# Sheet_2_2022-11-04.net
KiCad netlist of a schematic drawn in Altium Designer
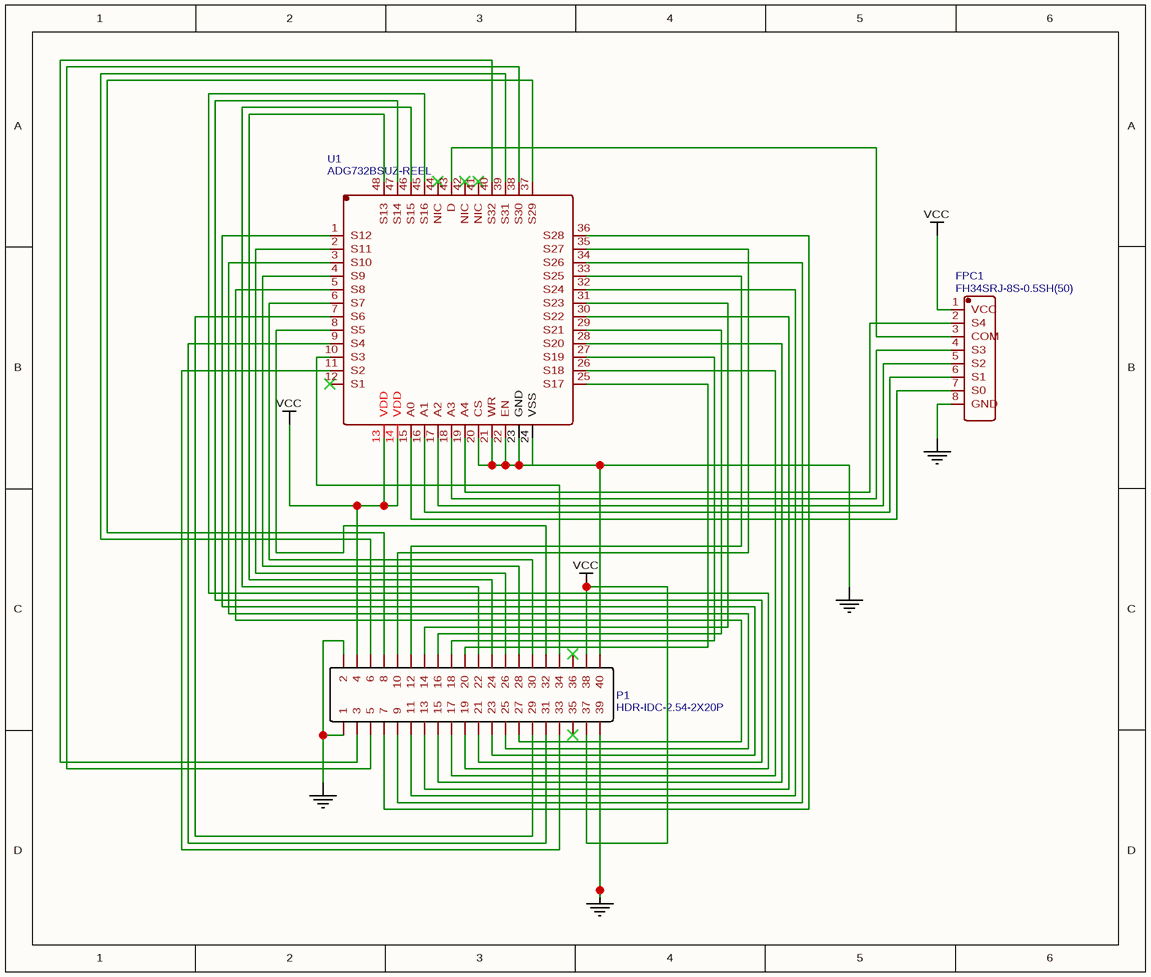
[diagram p0: Sheet_2_2022-11-04.schdoc]

(export (version "E")
  (design (tool "Eeschema 10.0.6"))
  (components
    (comp (ref "FPC1")
      (value "FH34SRJ-8S-0.5SH(50)")
      (fields (field (name "BOM_SUPPLIER PART") "C88372") (field (name "CONTRIBUTOR") "LCSC"))
      (libsource (lib "altium-import") (part "root_0_FH34SRJ-8S-0.5SH(50)_"))
    )
    (comp (ref "P1")
      (value "HDR-IDC-2.54-2X20P")
      (fields
        (field (name "BOM_MANUFACTURER PART") "IDC Box 2X20 2.54MM")
        (field (name "BOM_SUPPLIER PART") "C9138")
      )
      (libsource (lib "altium-import") (part "root_1_HDR-IDC-2.54-2X20P_"))
    )
    (comp (ref "U1")
      (value "ADG732BSUZ-REEL")
      (fields (field (name "BOM_SUPPLIER PART") "C114845") (field (name "CONTRIBUTOR") "LCSC"))
      (libsource (lib "altium-import") (part "root_0_ADG732BSUZ-REEL_"))
    )
  )
  (nets
    (net (code "1") (name "GND") (class "Default")
      (node (ref "FPC1") (pin "8") (pinfunction "GND_8") (pintype "passive"))
      (node (ref "P1") (pin "1") (pinfunction "1_1") (pintype "passive"))
      (node (ref "P1") (pin "2") (pinfunction "2_2") (pintype "passive"))
      (node (ref "P1") (pin "39") (pinfunction "39_39") (pintype "passive"))
      (node (ref "P1") (pin "40") (pinfunction "40_40") (pintype "passive"))
      (node (ref "U1") (pin "20") (pinfunction "CS_20") (pintype "passive"))
      (node (ref "U1") (pin "21") (pinfunction "WR_21") (pintype "passive"))
      (node (ref "U1") (pin "22") (pinfunction "EN_22") (pintype "passive"))
      (node (ref "U1") (pin "23") (pinfunction "GND_23") (pintype "passive"))
      (node (ref "U1") (pin "24") (pinfunction "VSS_24") (pintype "passive"))
    )
    (net (code "2") (name "Net-(FPC1-COM)") (class "Default")
      (node (ref "FPC1") (pin "3") (pinfunction "COM_3") (pintype "passive"))
      (node (ref "U1") (pin "43") (pinfunction "D_43") (pintype "passive"))
    )
    (net (code "3") (name "Net-(FPC1-S0)") (class "Default")
      (node (ref "FPC1") (pin "7") (pinfunction "S0_7") (pintype "passive"))
      (node (ref "U1") (pin "15") (pinfunction "A0_15") (pintype "passive"))
    )
    (net (code "4") (name "Net-(FPC1-S1)") (class "Default")
      (node (ref "FPC1") (pin "6") (pinfunction "S1_6") (pintype "passive"))
      (node (ref "U1") (pin "16") (pinfunction "A1_16") (pintype "passive"))
    )
    (net (code "5") (name "Net-(FPC1-S2)") (class "Default")
      (node (ref "FPC1") (pin "5") (pinfunction "S2_5") (pintype "passive"))
      (node (ref "U1") (pin "17") (pinfunction "A2_17") (pintype "passive"))
    )
    (net (code "6") (name "Net-(FPC1-S3)") (class "Default")
      (node (ref "FPC1") (pin "4") (pinfunction "S3_4") (pintype "passive"))
      (node (ref "U1") (pin "18") (pinfunction "A3_18") (pintype "passive"))
    )
    (net (code "7") (name "Net-(FPC1-S4)") (class "Default")
      (node (ref "FPC1") (pin "2") (pinfunction "S4_2") (pintype "passive"))
      (node (ref "U1") (pin "19") (pinfunction "A4_19") (pintype "passive"))
    )
    (net (code "8") (name "Net-(U1-S2)") (class "Default")
      (node (ref "P1") (pin "33") (pinfunction "33_33") (pintype "passive"))
      (node (ref "U1") (pin "11") (pinfunction "S2_11") (pintype "passive"))
    )
    (net (code "9") (name "Net-(U1-S3)") (class "Default")
      (node (ref "P1") (pin "34") (pinfunction "34_34") (pintype "passive"))
      (node (ref "U1") (pin "10") (pinfunction "S3_10") (pintype "passive"))
    )
    (net (code "10") (name "Net-(U1-S4)") (class "Default")
      (node (ref "P1") (pin "31") (pinfunction "31_31") (pintype "passive"))
      (node (ref "U1") (pin "9") (pinfunction "S4_9") (pintype "passive"))
    )
    (net (code "11") (name "Net-(U1-S5)") (class "Default")
      (node (ref "P1") (pin "32") (pinfunction "32_32") (pintype "passive"))
      (node (ref "U1") (pin "8") (pinfunction "S5_8") (pintype "passive"))
    )
    (net (code "12") (name "Net-(U1-S6)") (class "Default")
      (node (ref "P1") (pin "29") (pinfunction "29_29") (pintype "passive"))
      (node (ref "U1") (pin "7") (pinfunction "S6_7") (pintype "passive"))
    )
    (net (code "13") (name "Net-(U1-S7)") (class "Default")
      (node (ref "P1") (pin "30") (pinfunction "30_30") (pintype "passive"))
      (node (ref "U1") (pin "6") (pinfunction "S7_6") (pintype "passive"))
    )
    (net (code "14") (name "Net-(U1-S8)") (class "Default")
      (node (ref "P1") (pin "27") (pinfunction "27_27") (pintype "passive"))
      (node (ref "U1") (pin "5") (pinfunction "S8_5") (pintype "passive"))
    )
    (net (code "15") (name "Net-(U1-S9)") (class "Default")
      (node (ref "P1") (pin "28") (pinfunction "28_28") (pintype "passive"))
      (node (ref "U1") (pin "4") (pinfunction "S9_4") (pintype "passive"))
    )
    (net (code "16") (name "Net-(U1-S10)") (class "Default")
      (node (ref "P1") (pin "25") (pinfunction "25_25") (pintype "passive"))
      (node (ref "U1") (pin "3") (pinfunction "S10_3") (pintype "passive"))
    )
    (net (code "17") (name "Net-(U1-S11)") (class "Default")
      (node (ref "P1") (pin "26") (pinfunction "26_26") (pintype "passive"))
      (node (ref "U1") (pin "2") (pinfunction "S11_2") (pintype "passive"))
    )
    (net (code "18") (name "Net-(U1-S12)") (class "Default")
      (node (ref "P1") (pin "23") (pinfunction "23_23") (pintype "passive"))
      (node (ref "U1") (pin "1") (pinfunction "S12_1") (pintype "passive"))
    )
    (net (code "19") (name "Net-(U1-S13)") (class "Default")
      (node (ref "P1") (pin "24") (pinfunction "24_24") (pintype "passive"))
      (node (ref "U1") (pin "48") (pinfunction "S13_48") (pintype "passive"))
    )
    (net (code "20") (name "Net-(U1-S14)") (class "Default")
      (node (ref "P1") (pin "21") (pinfunction "21_21") (pintype "passive"))
      (node (ref "U1") (pin "47") (pinfunction "S14_47") (pintype "passive"))
    )
    (net (code "21") (name "Net-(U1-S15)") (class "Default")
      (node (ref "P1") (pin "22") (pinfunction "22_22") (pintype "passive"))
      (node (ref "U1") (pin "46") (pinfunction "S15_46") (pintype "passive"))
    )
    (net (code "22") (name "Net-(U1-S16)") (class "Default")
      (node (ref "P1") (pin "19") (pinfunction "19_19") (pintype "passive"))
      (node (ref "U1") (pin "45") (pinfunction "S16_45") (pintype "passive"))
    )
    (net (code "23") (name "Net-(U1-S17)") (class "Default")
      (node (ref "P1") (pin "20") (pinfunction "20_20") (pintype "passive"))
      (node (ref "U1") (pin "25") (pinfunction "S17_25") (pintype "passive"))
    )
    (net (code "24") (name "Net-(U1-S18)") (class "Default")
      (node (ref "P1") (pin "17") (pinfunction "17_17") (pintype "passive"))
      (node (ref "U1") (pin "26") (pinfunction "S18_26") (pintype "passive"))
    )
    (net (code "25") (name "Net-(U1-S19)") (class "Default")
      (node (ref "P1") (pin "18") (pinfunction "18_18") (pintype "passive"))
      (node (ref "U1") (pin "27") (pinfunction "S19_27") (pintype "passive"))
    )
    (net (code "26") (name "Net-(U1-S20)") (class "Default")
      (node (ref "P1") (pin "15") (pinfunction "15_15") (pintype "passive"))
      (node (ref "U1") (pin "28") (pinfunction "S20_28") (pintype "passive"))
    )
    (net (code "27") (name "Net-(U1-S21)") (class "Default")
      (node (ref "P1") (pin "16") (pinfunction "16_16") (pintype "passive"))
      (node (ref "U1") (pin "29") (pinfunction "S21_29") (pintype "passive"))
    )
    (net (code "28") (name "Net-(U1-S22)") (class "Default")
      (node (ref "P1") (pin "13") (pinfunction "13_13") (pintype "passive"))
      (node (ref "U1") (pin "30") (pinfunction "S22_30") (pintype "passive"))
    )
    (net (code "29") (name "Net-(U1-S23)") (class "Default")
      (node (ref "P1") (pin "14") (pinfunction "14_14") (pintype "passive"))
      (node (ref "U1") (pin "31") (pinfunction "S23_31") (pintype "passive"))
    )
    (net (code "30") (name "Net-(U1-S24)") (class "Default")
      (node (ref "P1") (pin "11") (pinfunction "11_11") (pintype "passive"))
      (node (ref "U1") (pin "32") (pinfunction "S24_32") (pintype "passive"))
    )
    (net (code "31") (name "Net-(U1-S25)") (class "Default")
      (node (ref "P1") (pin "12") (pinfunction "12_12") (pintype "passive"))
      (node (ref "U1") (pin "33") (pinfunction "S25_33") (pintype "passive"))
    )
    (net (code "32") (name "Net-(U1-S26)") (class "Default")
      (node (ref "P1") (pin "9") (pinfunction "9_9") (pintype "passive"))
      (node (ref "U1") (pin "34") (pinfunction "S26_34") (pintype "passive"))
    )
    (net (code "33") (name "Net-(U1-S27)") (class "Default")
      (node (ref "P1") (pin "10") (pinfunction "10_10") (pintype "passive"))
      (node (ref "U1") (pin "35") (pinfunction "S27_35") (pintype "passive"))
    )
    (net (code "34") (name "Net-(U1-S28)") (class "Default")
      (node (ref "P1") (pin "7") (pinfunction "7_7") (pintype "passive"))
      (node (ref "U1") (pin "36") (pinfunction "S28_36") (pintype "passive"))
    )
    (net (code "35") (name "Net-(U1-S29)") (class "Default")
      (node (ref "P1") (pin "8") (pinfunction "8_8") (pintype "passive"))
      (node (ref "U1") (pin "37") (pinfunction "S29_37") (pintype "passive"))
    )
    (net (code "36") (name "Net-(U1-S30)") (class "Default")
      (node (ref "P1") (pin "5") (pinfunction "5_5") (pintype "passive"))
      (node (ref "U1") (pin "38") (pinfunction "S30_38") (pintype "passive"))
    )
    (net (code "37") (name "Net-(U1-S31)") (class "Default")
      (node (ref "P1") (pin "6") (pinfunction "6_6") (pintype "passive"))
      (node (ref "U1") (pin "39") (pinfunction "S31_39") (pintype "passive"))
    )
    (net (code "38") (name "Net-(U1-S32)") (class "Default")
      (node (ref "P1") (pin "3") (pinfunction "3_3") (pintype "passive"))
      (node (ref "U1") (pin "40") (pinfunction "S32_40") (pintype "passive"))
    )
    (net (code "39") (name "VCC") (class "Default")
      (node (ref "FPC1") (pin "1") (pinfunction "VCC_1") (pintype "passive"))
      (node (ref "P1") (pin "37") (pinfunction "37_37") (pintype "passive"))
      (node (ref "P1") (pin "38") (pinfunction "38_38") (pintype "passive"))
      (node (ref "P1") (pin "4") (pinfunction "4_4") (pintype "passive"))
      (node (ref "U1") (pin "13") (pinfunction "VDD_13") (pintype "passive"))
      (node (ref "U1") (pin "14") (pinfunction "VDD_14") (pintype "passive"))
    )
    (net (code "40") (name "unconnected-(P1-Pad35)") (class "Default")
      (node (ref "P1") (pin "35") (pinfunction "35_35") (pintype "passive+no_connect"))
    )
    (net (code "41") (name "unconnected-(P1-Pad36)") (class "Default")
      (node (ref "P1") (pin "36") (pinfunction "36_36") (pintype "passive+no_connect"))
    )
    (net (code "42") (name "unconnected-(U1-NIC-Pad41)") (class "Default")
      (node (ref "U1") (pin "41") (pinfunction "NIC_41") (pintype "passive+no_connect"))
    )
    (net (code "43") (name "unconnected-(U1-NIC-Pad42)") (class "Default")
      (node (ref "U1") (pin "42") (pinfunction "NIC_42") (pintype "passive+no_connect"))
    )
    (net (code "44") (name "unconnected-(U1-NIC-Pad44)") (class "Default")
      (node (ref "U1") (pin "44") (pinfunction "NIC_44") (pintype "passive+no_connect"))
    )
    (net (code "45") (name "unconnected-(U1-S1-Pad12)") (class "Default")
      (node (ref "U1") (pin "12") (pinfunction "S1_12") (pintype "passive+no_connect"))
    )
  )
)
